# rev1.net
KiCad netlist of a schematic drawn in EAGLE
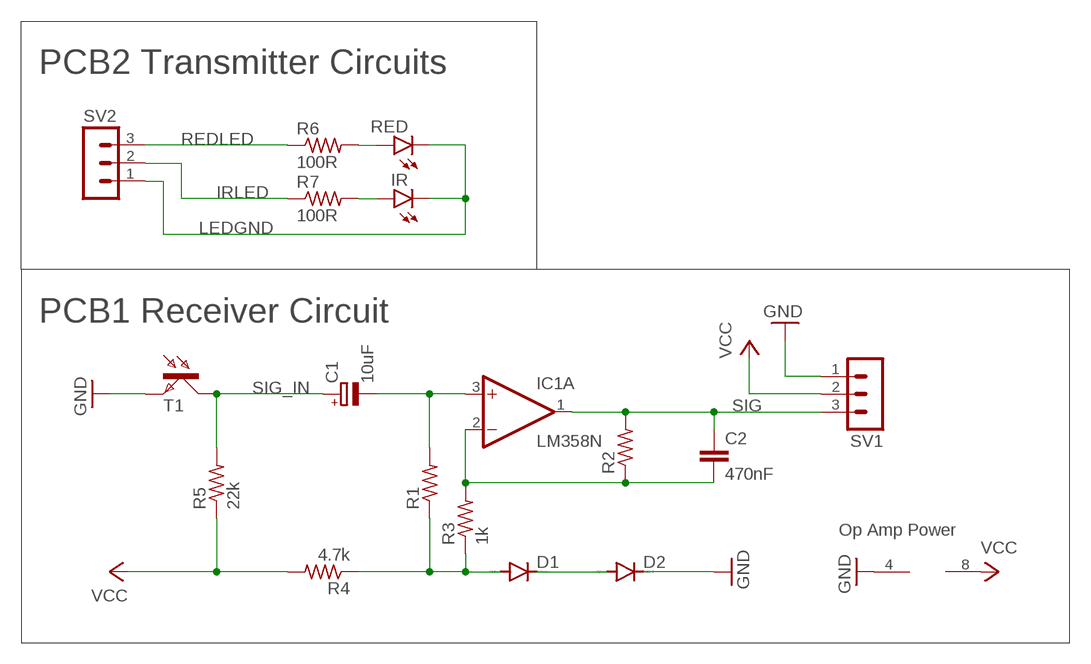
[diagram p0: schematic, sheet 1]

(export (version "E")
  (design (tool "Eeschema 10.0.6"))
  (components
    (comp (ref "C1")
      (value "10uF")
      (footprint "eagle-import:R_2012-12R")
      (libsource (lib "eagle-import") (part "CPOL-EUR/2012-12R"))
    )
    (comp (ref "C2")
      (value "470nF")
      (footprint "eagle-import:C2.5-3")
      (libsource (lib "eagle-import") (part "C2,5-3"))
    )
    (comp (ref "D1")
      (value "1N4148DO35-7")
      (footprint "eagle-import:DO35-7")
      (libsource (lib "eagle-import") (part "1N4148DO35-7"))
    )
    (comp (ref "D2")
      (value "1N4148DO35-7")
      (footprint "eagle-import:DO35-7")
      (libsource (lib "eagle-import") (part "1N4148DO35-7"))
    )
    (comp (ref "IC1")
      (value "LM358N")
      (footprint "eagle-import:DIL08")
      (libsource (lib "eagle-import") (part "LM358N"))
    )
    (comp (ref "IR")
      (value "LEDIRL80A")
      (footprint "eagle-import:IRL80A")
      (libsource (lib "eagle-import") (part "LEDIRL80A"))
    )
    (comp (ref "R1")
      (value "R-US_0207/7")
      (footprint "eagle-import:0207_7")
      (libsource (lib "eagle-import") (part "R-US_0207/7"))
    )
    (comp (ref "R2")
      (value "R-US_0207/7")
      (footprint "eagle-import:0207_7")
      (libsource (lib "eagle-import") (part "R-US_0207/7"))
    )
    (comp (ref "R3")
      (value "1k")
      (footprint "eagle-import:R0805")
      (libsource (lib "eagle-import") (part "R-US_R0805"))
    )
    (comp (ref "R4")
      (value "4.7k")
      (footprint "eagle-import:0207_7")
      (libsource (lib "eagle-import") (part "R-US_0207/7"))
    )
    (comp (ref "R5")
      (value "22k")
      (footprint "eagle-import:0207_7")
      (libsource (lib "eagle-import") (part "R-US_0207/7"))
    )
    (comp (ref "R6")
      (value "100R")
      (footprint "eagle-import:R0805")
      (libsource (lib "eagle-import") (part "R-US_R0805"))
    )
    (comp (ref "R7")
      (value "100R")
      (footprint "eagle-import:R0805")
      (libsource (lib "eagle-import") (part "R-US_R0805"))
    )
    (comp (ref "RED")
      (value "LEDCHIPLED_0805")
      (footprint "eagle-import:CHIPLED_0805")
      (libsource (lib "eagle-import") (part "LEDCHIPLED_0805"))
    )
    (comp (ref "SV1")
      (value "MA03-1")
      (footprint "eagle-import:MA03-1")
      (libsource (lib "eagle-import") (part "MA03-1"))
    )
    (comp (ref "SV2")
      (value "MA03-1")
      (footprint "eagle-import:MA03-1")
      (libsource (lib "eagle-import") (part "MA03-1"))
    )
    (comp (ref "T1")
      (value "LPT80A")
      (footprint "eagle-import:LPT80A")
      (libsource (lib "eagle-import") (part "LPT80A"))
    )
  )
  (nets
    (net (code "1") (name "/IRLED") (class "Default")
      (node (ref "R7") (pin "1") (pinfunction "1_1") (pintype "passive"))
      (node (ref "SV2") (pin "2") (pinfunction "2_2") (pintype "passive"))
    )
    (net (code "2") (name "/LEDGND") (class "Default")
      (node (ref "IR") (pin "K") (pinfunction "C_K") (pintype "passive"))
      (node (ref "RED") (pin "C") (pinfunction "C_C") (pintype "passive"))
      (node (ref "SV2") (pin "1") (pinfunction "1_1") (pintype "passive"))
    )
    (net (code "3") (name "/REDLED") (class "Default")
      (node (ref "R6") (pin "1") (pinfunction "1_1") (pintype "passive"))
      (node (ref "SV2") (pin "3") (pinfunction "3_3") (pintype "passive"))
    )
    (net (code "4") (name "/SIG") (class "Default")
      (node (ref "C2") (pin "1") (pinfunction "1_1") (pintype "passive"))
      (node (ref "IC1") (pin "1") (pinfunction "OUT_1") (pintype "output"))
      (node (ref "R2") (pin "2") (pinfunction "2_2") (pintype "passive"))
      (node (ref "SV1") (pin "3") (pinfunction "3_3") (pintype "passive"))
    )
    (net (code "5") (name "/SIG_IN") (class "Default")
      (node (ref "C1") (pin "+") (pinfunction "+_+") (pintype "passive"))
      (node (ref "R5") (pin "2") (pinfunction "2_2") (pintype "passive"))
      (node (ref "T1") (pin "C") (pinfunction "C_C") (pintype "passive"))
    )
    (net (code "6") (name "GND") (class "Default")
      (node (ref "D2") (pin "C") (pinfunction "C_C") (pintype "passive"))
      (node (ref "IC1") (pin "4") (pinfunction "V-_4") (pintype "power_in"))
      (node (ref "SV1") (pin "1") (pinfunction "1_1") (pintype "passive"))
      (node (ref "T1") (pin "E") (pinfunction "E_E") (pintype "passive"))
    )
    (net (code "7") (name "Net-(D1-PadA)") (class "Default")
      (node (ref "D1") (pin "A") (pinfunction "A_A") (pintype "passive"))
      (node (ref "R1") (pin "1") (pinfunction "1_1") (pintype "passive"))
      (node (ref "R3") (pin "1") (pinfunction "1_1") (pintype "passive"))
      (node (ref "R4") (pin "1") (pinfunction "1_1") (pintype "passive"))
    )
    (net (code "8") (name "Net-(D1-PadC)") (class "Default")
      (node (ref "D1") (pin "C") (pinfunction "C_C") (pintype "passive"))
      (node (ref "D2") (pin "A") (pinfunction "A_A") (pintype "passive"))
    )
    (net (code "9") (name "Net-(IC1A-+IN)") (class "Default")
      (node (ref "C1") (pin "-") (pinfunction "-_-") (pintype "passive"))
      (node (ref "IC1") (pin "3") (pinfunction "+IN_3") (pintype "input"))
      (node (ref "R1") (pin "2") (pinfunction "2_2") (pintype "passive"))
    )
    (net (code "10") (name "Net-(IC1A--IN)") (class "Default")
      (node (ref "C2") (pin "2") (pinfunction "2_2") (pintype "passive"))
      (node (ref "IC1") (pin "2") (pinfunction "-IN_2") (pintype "input"))
      (node (ref "R2") (pin "1") (pinfunction "1_1") (pintype "passive"))
      (node (ref "R3") (pin "2") (pinfunction "2_2") (pintype "passive"))
    )
    (net (code "11") (name "Net-(IR-PadA)") (class "Default")
      (node (ref "IR") (pin "A") (pinfunction "A_A") (pintype "passive"))
      (node (ref "R7") (pin "2") (pinfunction "2_2") (pintype "passive"))
    )
    (net (code "12") (name "Net-(R6-Pad2)") (class "Default")
      (node (ref "R6") (pin "2") (pinfunction "2_2") (pintype "passive"))
      (node (ref "RED") (pin "A") (pinfunction "A_A") (pintype "passive"))
    )
    (net (code "13") (name "VCC") (class "Default")
      (node (ref "IC1") (pin "8") (pinfunction "V+_8") (pintype "power_in"))
      (node (ref "R4") (pin "2") (pinfunction "2_2") (pintype "passive"))
      (node (ref "R5") (pin "1") (pinfunction "1_1") (pintype "passive"))
      (node (ref "SV1") (pin "2") (pinfunction "2_2") (pintype "passive"))
    )
  )
)
